# A7_FUNCTION3_-.net
KiCad netlist of a schematic drawn in Altium Designer
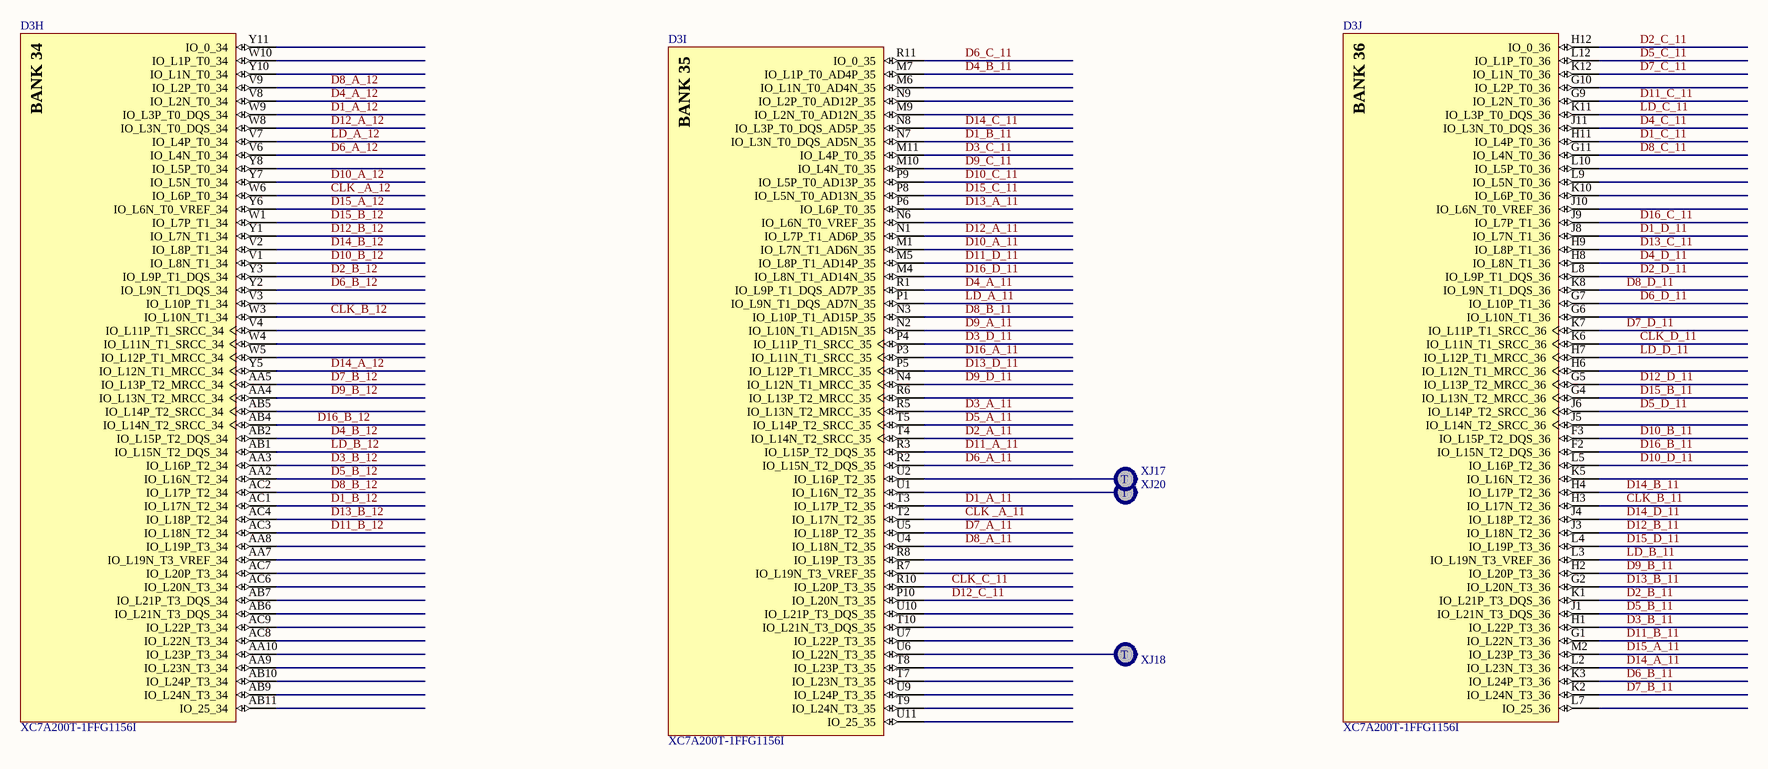
[diagram p0: A7_FUNCTION3 - Ⅱ.SchDoc]

(export (version "E")
  (design (tool "Eeschema 10.0.6"))
  (components
    (comp (ref "D3")
      (value "XC7A200T-1FFG1156I")
      (footprint "FFG1156")
      (description "Artix-7 FPGA, 500 User I/Os, 16 GTP, 1156-Ball BGA, Speed Grade 1, Industrial Grade, Pb-Free")
      (fields (field (name "GENERIC PART NUMBER") "XC7A200T") (field (name "MANUFACTURER") "Xilinx"))
      (libsource (lib "Xilinx Artix-7") (part "XC7A200T-1FFG1156I"))
    )
    (comp (ref "XJ17")
      (value "TESTPOINT")
      (footprint "TEST-pin")
      (description "测试点")
      (libsource (lib "Database_Libs1") (part "TESTPOINT"))
    )
    (comp (ref "XJ18")
      (value "TESTPOINT")
      (footprint "TEST-pin")
      (description "测试点")
      (libsource (lib "Database_Libs1") (part "TESTPOINT"))
    )
    (comp (ref "XJ20")
      (value "TESTPOINT")
      (footprint "TEST-pin")
      (description "测试点")
      (libsource (lib "Database_Libs1") (part "TESTPOINT"))
    )
  )
  (nets
    (net (code "1") (name "/CLK _A_11") (class "Default")
      (node (ref "D3") (pin "T2") (pinfunction "IO_L17N_T2_35_T2") (pintype "bidirectional"))
    )
    (net (code "2") (name "/CLK _A_12") (class "Default")
      (node (ref "D3") (pin "W6") (pinfunction "IO_L6P_T0_34_W6") (pintype "bidirectional"))
    )
    (net (code "3") (name "/CLK_B_11") (class "Default")
      (node (ref "D3") (pin "H3") (pinfunction "IO_L17N_T2_36_H3") (pintype "bidirectional"))
    )
    (net (code "4") (name "/CLK_B_12") (class "Default")
      (node (ref "D3") (pin "W3") (pinfunction "IO_L10N_T1_34_W3") (pintype "bidirectional"))
    )
    (net (code "5") (name "/CLK_C_11") (class "Default")
      (node (ref "D3") (pin "R10") (pinfunction "IO_L20P_T3_35_R10") (pintype "bidirectional"))
    )
    (net (code "6") (name "/CLK_D_11") (class "Default")
      (node (ref "D3") (pin "K6") (pinfunction "IO_L11N_T1_SRCC_36_K6") (pintype "bidirectional"))
    )
    (net (code "7") (name "/D1_A_11") (class "Default")
      (node (ref "D3") (pin "T3") (pinfunction "IO_L17P_T2_35_T3") (pintype "bidirectional"))
    )
    (net (code "8") (name "/D1_A_12") (class "Default")
      (node (ref "D3") (pin "W9") (pinfunction "IO_L3P_T0_DQS_34_W9") (pintype "bidirectional"))
    )
    (net (code "9") (name "/D1_B_11") (class "Default")
      (node (ref "D3") (pin "N7") (pinfunction "IO_L3N_T0_DQS_AD5N_35_N7") (pintype "bidirectional"))
    )
    (net (code "10") (name "/D1_B_12") (class "Default")
      (node (ref "D3") (pin "AC1") (pinfunction "IO_L17N_T2_34_AC1") (pintype "bidirectional"))
    )
    (net (code "11") (name "/D1_C_11") (class "Default")
      (node (ref "D3") (pin "H11") (pinfunction "IO_L4P_T0_36_H11") (pintype "bidirectional"))
    )
    (net (code "12") (name "/D1_D_11") (class "Default")
      (node (ref "D3") (pin "J8") (pinfunction "IO_L7N_T1_36_J8") (pintype "bidirectional"))
    )
    (net (code "13") (name "/D2_A_11") (class "Default")
      (node (ref "D3") (pin "T4") (pinfunction "IO_L14N_T2_SRCC_35_T4") (pintype "bidirectional"))
    )
    (net (code "14") (name "/D2_B_11") (class "Default")
      (node (ref "D3") (pin "K1") (pinfunction "IO_L21P_T3_DQS_36_K1") (pintype "bidirectional"))
    )
    (net (code "15") (name "/D2_B_12") (class "Default")
      (node (ref "D3") (pin "Y3") (pinfunction "IO_L9P_T1_DQS_34_Y3") (pintype "bidirectional"))
    )
    (net (code "16") (name "/D2_C_11") (class "Default")
      (node (ref "D3") (pin "H12") (pinfunction "IO_0_36_H12") (pintype "bidirectional"))
    )
    (net (code "17") (name "/D2_D_11") (class "Default")
      (node (ref "D3") (pin "L8") (pinfunction "IO_L9P_T1_DQS_36_L8") (pintype "bidirectional"))
    )
    (net (code "18") (name "/D3_A_11") (class "Default")
      (node (ref "D3") (pin "R5") (pinfunction "IO_L13N_T2_MRCC_35_R5") (pintype "bidirectional"))
    )
    (net (code "19") (name "/D3_B_11") (class "Default")
      (node (ref "D3") (pin "H1") (pinfunction "IO_L22P_T3_36_H1") (pintype "bidirectional"))
    )
    (net (code "20") (name "/D3_B_12") (class "Default")
      (node (ref "D3") (pin "AA3") (pinfunction "IO_L16P_T2_34_AA3") (pintype "bidirectional"))
    )
    (net (code "21") (name "/D3_C_11") (class "Default")
      (node (ref "D3") (pin "M11") (pinfunction "IO_L4P_T0_35_M11") (pintype "bidirectional"))
    )
    (net (code "22") (name "/D3_D_11") (class "Default")
      (node (ref "D3") (pin "P4") (pinfunction "IO_L11P_T1_SRCC_35_P4") (pintype "bidirectional"))
    )
    (net (code "23") (name "/D4_A_11") (class "Default")
      (node (ref "D3") (pin "R1") (pinfunction "IO_L9P_T1_DQS_AD7P_35_R1") (pintype "bidirectional"))
    )
    (net (code "24") (name "/D4_A_12") (class "Default")
      (node (ref "D3") (pin "V8") (pinfunction "IO_L2N_T0_34_V8") (pintype "bidirectional"))
    )
    (net (code "25") (name "/D4_B_11") (class "Default")
      (node (ref "D3") (pin "M7") (pinfunction "IO_L1P_T0_AD4P_35_M7") (pintype "bidirectional"))
    )
    (net (code "26") (name "/D4_B_12") (class "Default")
      (node (ref "D3") (pin "AB2") (pinfunction "IO_L15P_T2_DQS_34_AB2") (pintype "bidirectional"))
    )
    (net (code "27") (name "/D4_C_11") (class "Default")
      (node (ref "D3") (pin "J11") (pinfunction "IO_L3N_T0_DQS_36_J11") (pintype "bidirectional"))
    )
    (net (code "28") (name "/D4_D_11") (class "Default")
      (node (ref "D3") (pin "H8") (pinfunction "IO_L8N_T1_36_H8") (pintype "bidirectional"))
    )
    (net (code "29") (name "/D5_A_11") (class "Default")
      (node (ref "D3") (pin "T5") (pinfunction "IO_L14P_T2_SRCC_35_T5") (pintype "bidirectional"))
    )
    (net (code "30") (name "/D5_B_11") (class "Default")
      (node (ref "D3") (pin "J1") (pinfunction "IO_L21N_T3_DQS_36_J1") (pintype "bidirectional"))
    )
    (net (code "31") (name "/D5_B_12") (class "Default")
      (node (ref "D3") (pin "AA2") (pinfunction "IO_L16N_T2_34_AA2") (pintype "bidirectional"))
    )
    (net (code "32") (name "/D5_C_11") (class "Default")
      (node (ref "D3") (pin "L12") (pinfunction "IO_L1P_T0_36_L12") (pintype "bidirectional"))
    )
    (net (code "33") (name "/D5_D_11") (class "Default")
      (node (ref "D3") (pin "J6") (pinfunction "IO_L14P_T2_SRCC_36_J6") (pintype "bidirectional"))
    )
    (net (code "34") (name "/D6_A_11") (class "Default")
      (node (ref "D3") (pin "R2") (pinfunction "IO_L15N_T2_DQS_35_R2") (pintype "bidirectional"))
    )
    (net (code "35") (name "/D6_A_12") (class "Default")
      (node (ref "D3") (pin "V6") (pinfunction "IO_L4N_T0_34_V6") (pintype "bidirectional"))
    )
    (net (code "36") (name "/D6_B_11") (class "Default")
      (node (ref "D3") (pin "K3") (pinfunction "IO_L24P_T3_36_K3") (pintype "bidirectional"))
    )
    (net (code "37") (name "/D6_B_12") (class "Default")
      (node (ref "D3") (pin "Y2") (pinfunction "IO_L9N_T1_DQS_34_Y2") (pintype "bidirectional"))
    )
    (net (code "38") (name "/D6_C_11") (class "Default")
      (node (ref "D3") (pin "R11") (pinfunction "IO_0_35_R11") (pintype "bidirectional"))
    )
    (net (code "39") (name "/D6_D_11") (class "Default")
      (node (ref "D3") (pin "G7") (pinfunction "IO_L10P_T1_36_G7") (pintype "bidirectional"))
    )
    (net (code "40") (name "/D7_A_11") (class "Default")
      (node (ref "D3") (pin "U5") (pinfunction "IO_L18P_T2_35_U5") (pintype "bidirectional"))
    )
    (net (code "41") (name "/D7_B_11") (class "Default")
      (node (ref "D3") (pin "K2") (pinfunction "IO_L24N_T3_36_K2") (pintype "bidirectional"))
    )
    (net (code "42") (name "/D7_B_12") (class "Default")
      (node (ref "D3") (pin "AA5") (pinfunction "IO_L13P_T2_MRCC_34_AA5") (pintype "bidirectional"))
    )
    (net (code "43") (name "/D7_C_11") (class "Default")
      (node (ref "D3") (pin "K12") (pinfunction "IO_L1N_T0_36_K12") (pintype "bidirectional"))
    )
    (net (code "44") (name "/D7_D_11") (class "Default")
      (node (ref "D3") (pin "K7") (pinfunction "IO_L11P_T1_SRCC_36_K7") (pintype "bidirectional"))
    )
    (net (code "45") (name "/D8_A_11") (class "Default")
      (node (ref "D3") (pin "U4") (pinfunction "IO_L18N_T2_35_U4") (pintype "bidirectional"))
    )
    (net (code "46") (name "/D8_A_12") (class "Default")
      (node (ref "D3") (pin "V9") (pinfunction "IO_L2P_T0_34_V9") (pintype "bidirectional"))
    )
    (net (code "47") (name "/D8_B_11") (class "Default")
      (node (ref "D3") (pin "N3") (pinfunction "IO_L10P_T1_AD15P_35_N3") (pintype "bidirectional"))
    )
    (net (code "48") (name "/D8_B_12") (class "Default")
      (node (ref "D3") (pin "AC2") (pinfunction "IO_L17P_T2_34_AC2") (pintype "bidirectional"))
    )
    (net (code "49") (name "/D8_C_11") (class "Default")
      (node (ref "D3") (pin "G11") (pinfunction "IO_L4N_T0_36_G11") (pintype "bidirectional"))
    )
    (net (code "50") (name "/D8_D_11") (class "Default")
      (node (ref "D3") (pin "K8") (pinfunction "IO_L9N_T1_DQS_36_K8") (pintype "bidirectional"))
    )
    (net (code "51") (name "/D9_A_11") (class "Default")
      (node (ref "D3") (pin "N2") (pinfunction "IO_L10N_T1_AD15N_35_N2") (pintype "bidirectional"))
    )
    (net (code "52") (name "/D9_B_11") (class "Default")
      (node (ref "D3") (pin "H2") (pinfunction "IO_L20P_T3_36_H2") (pintype "bidirectional"))
    )
    (net (code "53") (name "/D9_B_12") (class "Default")
      (node (ref "D3") (pin "AA4") (pinfunction "IO_L13N_T2_MRCC_34_AA4") (pintype "bidirectional"))
    )
    (net (code "54") (name "/D9_C_11") (class "Default")
      (node (ref "D3") (pin "M10") (pinfunction "IO_L4N_T0_35_M10") (pintype "bidirectional"))
    )
    (net (code "55") (name "/D9_D_11") (class "Default")
      (node (ref "D3") (pin "N4") (pinfunction "IO_L12N_T1_MRCC_35_N4") (pintype "bidirectional"))
    )
    (net (code "56") (name "/D10_A_11") (class "Default")
      (node (ref "D3") (pin "M1") (pinfunction "IO_L7N_T1_AD6N_35_M1") (pintype "bidirectional"))
    )
    (net (code "57") (name "/D10_A_12") (class "Default")
      (node (ref "D3") (pin "Y7") (pinfunction "IO_L5N_T0_34_Y7") (pintype "bidirectional"))
    )
    (net (code "58") (name "/D10_B_11") (class "Default")
      (node (ref "D3") (pin "F3") (pinfunction "IO_L15P_T2_DQS_36_F3") (pintype "bidirectional"))
    )
    (net (code "59") (name "/D10_B_12") (class "Default")
      (node (ref "D3") (pin "V1") (pinfunction "IO_L8N_T1_34_V1") (pintype "bidirectional"))
    )
    (net (code "60") (name "/D10_C_11") (class "Default")
      (node (ref "D3") (pin "P9") (pinfunction "IO_L5P_T0_AD13P_35_P9") (pintype "bidirectional"))
    )
    (net (code "61") (name "/D10_D_11") (class "Default")
      (node (ref "D3") (pin "L5") (pinfunction "IO_L16P_T2_36_L5") (pintype "bidirectional"))
    )
    (net (code "62") (name "/D11_A_11") (class "Default")
      (node (ref "D3") (pin "R3") (pinfunction "IO_L15P_T2_DQS_35_R3") (pintype "bidirectional"))
    )
    (net (code "63") (name "/D11_B_11") (class "Default")
      (node (ref "D3") (pin "G1") (pinfunction "IO_L22N_T3_36_G1") (pintype "bidirectional"))
    )
    (net (code "64") (name "/D11_B_12") (class "Default")
      (node (ref "D3") (pin "AC3") (pinfunction "IO_L18N_T2_34_AC3") (pintype "bidirectional"))
    )
    (net (code "65") (name "/D11_C_11") (class "Default")
      (node (ref "D3") (pin "G9") (pinfunction "IO_L2N_T0_36_G9") (pintype "bidirectional"))
    )
    (net (code "66") (name "/D11_D_11") (class "Default")
      (node (ref "D3") (pin "M5") (pinfunction "IO_L8P_T1_AD14P_35_M5") (pintype "bidirectional"))
    )
    (net (code "67") (name "/D12_A_11") (class "Default")
      (node (ref "D3") (pin "N1") (pinfunction "IO_L7P_T1_AD6P_35_N1") (pintype "bidirectional"))
    )
    (net (code "68") (name "/D12_A_12") (class "Default")
      (node (ref "D3") (pin "W8") (pinfunction "IO_L3N_T0_DQS_34_W8") (pintype "bidirectional"))
    )
    (net (code "69") (name "/D12_B_11") (class "Default")
      (node (ref "D3") (pin "J3") (pinfunction "IO_L18N_T2_36_J3") (pintype "bidirectional"))
    )
    (net (code "70") (name "/D12_B_12") (class "Default")
      (node (ref "D3") (pin "Y1") (pinfunction "IO_L7N_T1_34_Y1") (pintype "bidirectional"))
    )
    (net (code "71") (name "/D12_C_11") (class "Default")
      (node (ref "D3") (pin "P10") (pinfunction "IO_L20N_T3_35_P10") (pintype "bidirectional"))
    )
    (net (code "72") (name "/D12_D_11") (class "Default")
      (node (ref "D3") (pin "G5") (pinfunction "IO_L13P_T2_MRCC_36_G5") (pintype "bidirectional"))
    )
    (net (code "73") (name "/D13_A_11") (class "Default")
      (node (ref "D3") (pin "P6") (pinfunction "IO_L6P_T0_35_P6") (pintype "bidirectional"))
    )
    (net (code "74") (name "/D13_B_11") (class "Default")
      (node (ref "D3") (pin "G2") (pinfunction "IO_L20N_T3_36_G2") (pintype "bidirectional"))
    )
    (net (code "75") (name "/D13_B_12") (class "Default")
      (node (ref "D3") (pin "AC4") (pinfunction "IO_L18P_T2_34_AC4") (pintype "bidirectional"))
    )
    (net (code "76") (name "/D13_C_11") (class "Default")
      (node (ref "D3") (pin "H9") (pinfunction "IO_L8P_T1_36_H9") (pintype "bidirectional"))
    )
    (net (code "77") (name "/D13_D_11") (class "Default")
      (node (ref "D3") (pin "P5") (pinfunction "IO_L12P_T1_MRCC_35_P5") (pintype "bidirectional"))
    )
    (net (code "78") (name "/D14_A_11") (class "Default")
      (node (ref "D3") (pin "L2") (pinfunction "IO_L23N_T3_36_L2") (pintype "bidirectional"))
    )
    (net (code "79") (name "/D14_A_12") (class "Default")
      (node (ref "D3") (pin "Y5") (pinfunction "IO_L12N_T1_MRCC_34_Y5") (pintype "bidirectional"))
    )
    (net (code "80") (name "/D14_B_11") (class "Default")
      (node (ref "D3") (pin "H4") (pinfunction "IO_L17P_T2_36_H4") (pintype "bidirectional"))
    )
    (net (code "81") (name "/D14_B_12") (class "Default")
      (node (ref "D3") (pin "V2") (pinfunction "IO_L8P_T1_34_V2") (pintype "bidirectional"))
    )
    (net (code "82") (name "/D14_C_11") (class "Default")
      (node (ref "D3") (pin "N8") (pinfunction "IO_L3P_T0_DQS_AD5P_35_N8") (pintype "bidirectional"))
    )
    (net (code "83") (name "/D14_D_11") (class "Default")
      (node (ref "D3") (pin "J4") (pinfunction "IO_L18P_T2_36_J4") (pintype "bidirectional"))
    )
    (net (code "84") (name "/D15_A_11") (class "Default")
      (node (ref "D3") (pin "M2") (pinfunction "IO_L23P_T3_36_M2") (pintype "bidirectional"))
    )
    (net (code "85") (name "/D15_A_12") (class "Default")
      (node (ref "D3") (pin "Y6") (pinfunction "IO_L6N_T0_VREF_34_Y6") (pintype "bidirectional"))
    )
    (net (code "86") (name "/D15_B_11") (class "Default")
      (node (ref "D3") (pin "G4") (pinfunction "IO_L13N_T2_MRCC_36_G4") (pintype "bidirectional"))
    )
    (net (code "87") (name "/D15_B_12") (class "Default")
      (node (ref "D3") (pin "W1") (pinfunction "IO_L7P_T1_34_W1") (pintype "bidirectional"))
    )
    (net (code "88") (name "/D15_C_11") (class "Default")
      (node (ref "D3") (pin "P8") (pinfunction "IO_L5N_T0_AD13N_35_P8") (pintype "bidirectional"))
    )
    (net (code "89") (name "/D15_D_11") (class "Default")
      (node (ref "D3") (pin "L4") (pinfunction "IO_L19P_T3_36_L4") (pintype "bidirectional"))
    )
    (net (code "90") (name "/D16_A_11") (class "Default")
      (node (ref "D3") (pin "P3") (pinfunction "IO_L11N_T1_SRCC_35_P3") (pintype "bidirectional"))
    )
    (net (code "91") (name "/D16_B_11") (class "Default")
      (node (ref "D3") (pin "F2") (pinfunction "IO_L15N_T2_DQS_36_F2") (pintype "bidirectional"))
    )
    (net (code "92") (name "/D16_B_12") (class "Default")
      (node (ref "D3") (pin "AB4") (pinfunction "IO_L14N_T2_SRCC_34_AB4") (pintype "bidirectional"))
    )
    (net (code "93") (name "/D16_C_11") (class "Default")
      (node (ref "D3") (pin "J9") (pinfunction "IO_L7P_T1_36_J9") (pintype "bidirectional"))
    )
    (net (code "94") (name "/D16_D_11") (class "Default")
      (node (ref "D3") (pin "M4") (pinfunction "IO_L8N_T1_AD14N_35_M4") (pintype "bidirectional"))
    )
    (net (code "95") (name "/LD_A_11") (class "Default")
      (node (ref "D3") (pin "P1") (pinfunction "IO_L9N_T1_DQS_AD7N_35_P1") (pintype "bidirectional"))
    )
    (net (code "96") (name "/LD_A_12") (class "Default")
      (node (ref "D3") (pin "V7") (pinfunction "IO_L4P_T0_34_V7") (pintype "bidirectional"))
    )
    (net (code "97") (name "/LD_B_11") (class "Default")
      (node (ref "D3") (pin "L3") (pinfunction "IO_L19N_T3_VREF_36_L3") (pintype "bidirectional"))
    )
    (net (code "98") (name "/LD_B_12") (class "Default")
      (node (ref "D3") (pin "AB1") (pinfunction "IO_L15N_T2_DQS_34_AB1") (pintype "bidirectional"))
    )
    (net (code "99") (name "/LD_C_11") (class "Default")
      (node (ref "D3") (pin "K11") (pinfunction "IO_L3P_T0_DQS_36_K11") (pintype "bidirectional"))
    )
    (net (code "100") (name "/LD_D_11") (class "Default")
      (node (ref "D3") (pin "H7") (pinfunction "IO_L12P_T1_MRCC_36_H7") (pintype "bidirectional"))
    )
    (net (code "101") (name "Net-(D3I-IO_L16N_T2_35)") (class "Default")
      (node (ref "D3") (pin "U1") (pinfunction "IO_L16N_T2_35_U1") (pintype "bidirectional"))
      (node (ref "XJ20") (pin "1") (pinfunction "T_1") (pintype "passive"))
    )
    (net (code "102") (name "Net-(D3I-IO_L16P_T2_35)") (class "Default")
      (node (ref "D3") (pin "U2") (pinfunction "IO_L16P_T2_35_U2") (pintype "bidirectional"))
      (node (ref "XJ17") (pin "1") (pinfunction "T_1") (pintype "passive"))
    )
    (net (code "103") (name "Net-(D3I-IO_L22N_T3_35)") (class "Default")
      (node (ref "D3") (pin "U6") (pinfunction "IO_L22N_T3_35_U6") (pintype "bidirectional"))
      (node (ref "XJ18") (pin "1") (pinfunction "T_1") (pintype "passive"))
    )
    (net (code "104") (name "unconnected-(D3H-IO_0_34-PadY11)") (class "Default")
      (node (ref "D3") (pin "Y11") (pinfunction "IO_0_34_Y11") (pintype "bidirectional"))
    )
    (net (code "105") (name "unconnected-(D3H-IO_25_34-PadAB11)") (class "Default")
      (node (ref "D3") (pin "AB11") (pinfunction "IO_25_34_AB11") (pintype "bidirectional"))
    )
    (net (code "106") (name "unconnected-(D3H-IO_L1N_T0_34-PadY10)") (class "Default")
      (node (ref "D3") (pin "Y10") (pinfunction "IO_L1N_T0_34_Y10") (pintype "bidirectional"))
    )
    (net (code "107") (name "unconnected-(D3H-IO_L1P_T0_34-PadW10)") (class "Default")
      (node (ref "D3") (pin "W10") (pinfunction "IO_L1P_T0_34_W10") (pintype "bidirectional"))
    )
    (net (code "108") (name "unconnected-(D3H-IO_L5P_T0_34-PadY8)") (class "Default")
      (node (ref "D3") (pin "Y8") (pinfunction "IO_L5P_T0_34_Y8") (pintype "bidirectional"))
    )
    (net (code "109") (name "unconnected-(D3H-IO_L10P_T1_34-PadV3)") (class "Default")
      (node (ref "D3") (pin "V3") (pinfunction "IO_L10P_T1_34_V3") (pintype "bidirectional"))
    )
    (net (code "110") (name "unconnected-(D3H-IO_L11N_T1_SRCC_34-PadW4)") (class "Default")
      (node (ref "D3") (pin "W4") (pinfunction "IO_L11N_T1_SRCC_34_W4") (pintype "bidirectional"))
    )
    (net (code "111") (name "unconnected-(D3H-IO_L11P_T1_SRCC_34-PadV4)") (class "Default")
      (node (ref "D3") (pin "V4") (pinfunction "IO_L11P_T1_SRCC_34_V4") (pintype "bidirectional"))
    )
    (net (code "112") (name "unconnected-(D3H-IO_L12P_T1_MRCC_34-PadW5)") (class "Default")
      (node (ref "D3") (pin "W5") (pinfunction "IO_L12P_T1_MRCC_34_W5") (pintype "bidirectional"))
    )
    (net (code "113") (name "unconnected-(D3H-IO_L14P_T2_SRCC_34-PadAB5)") (class "Default")
      (node (ref "D3") (pin "AB5") (pinfunction "IO_L14P_T2_SRCC_34_AB5") (pintype "bidirectional"))
    )
    (net (code "114") (name "unconnected-(D3H-IO_L19N_T3_VREF_34-PadAA7)") (class "Default")
      (node (ref "D3") (pin "AA7") (pinfunction "IO_L19N_T3_VREF_34_AA7") (pintype "bidirectional"))
    )
    (net (code "115") (name "unconnected-(D3H-IO_L19P_T3_34-PadAA8)") (class "Default")
      (node (ref "D3") (pin "AA8") (pinfunction "IO_L19P_T3_34_AA8") (pintype "bidirectional"))
    )
    (net (code "116") (name "unconnected-(D3H-IO_L20N_T3_34-PadAC6)") (class "Default")
      (node (ref "D3") (pin "AC6") (pinfunction "IO_L20N_T3_34_AC6") (pintype "bidirectional"))
    )
    (net (code "117") (name "unconnected-(D3H-IO_L20P_T3_34-PadAC7)") (class "Default")
      (node (ref "D3") (pin "AC7") (pinfunction "IO_L20P_T3_34_AC7") (pintype "bidirectional"))
    )
    (net (code "118") (name "unconnected-(D3H-IO_L21N_T3_DQS_34-PadAB6)") (class "Default")
      (node (ref "D3") (pin "AB6") (pinfunction "IO_L21N_T3_DQS_34_AB6") (pintype "bidirectional"))
    )
    (net (code "119") (name "unconnected-(D3H-IO_L21P_T3_DQS_34-PadAB7)") (class "Default")
      (node (ref "D3") (pin "AB7") (pinfunction "IO_L21P_T3_DQS_34_AB7") (pintype "bidirectional"))
    )
    (net (code "120") (name "unconnected-(D3H-IO_L22N_T3_34-PadAC8)") (class "Default")
      (node (ref "D3") (pin "AC8") (pinfunction "IO_L22N_T3_34_AC8") (pintype "bidirectional"))
    )
    (net (code "121") (name "unconnected-(D3H-IO_L22P_T3_34-PadAC9)") (class "Default")
      (node (ref "D3") (pin "AC9") (pinfunction "IO_L22P_T3_34_AC9") (pintype "bidirectional"))
    )
    (net (code "122") (name "unconnected-(D3H-IO_L23N_T3_34-PadAA9)") (class "Default")
      (node (ref "D3") (pin "AA9") (pinfunction "IO_L23N_T3_34_AA9") (pintype "bidirectional"))
    )
    (net (code "123") (name "unconnected-(D3H-IO_L23P_T3_34-PadAA10)") (class "Default")
      (node (ref "D3") (pin "AA10") (pinfunction "IO_L23P_T3_34_AA10") (pintype "bidirectional"))
    )
    (net (code "124") (name "unconnected-(D3H-IO_L24N_T3_34-PadAB9)") (class "Default")
      (node (ref "D3") (pin "AB9") (pinfunction "IO_L24N_T3_34_AB9") (pintype "bidirectional"))
    )
    (net (code "125") (name "unconnected-(D3H-IO_L24P_T3_34-PadAB10)") (class "Default")
      (node (ref "D3") (pin "AB10") (pinfunction "IO_L24P_T3_34_AB10") (pintype "bidirectional"))
    )
    (net (code "126") (name "unconnected-(D3I-IO_25_35-PadU11)") (class "Default")
      (node (ref "D3") (pin "U11") (pinfunction "IO_25_35_U11") (pintype "bidirectional"))
    )
    (net (code "127") (name "unconnected-(D3I-IO_L1N_T0_AD4N_35-PadM6)") (class "Default")
      (node (ref "D3") (pin "M6") (pinfunction "IO_L1N_T0_AD4N_35_M6") (pintype "bidirectional"))
    )
    (net (code "128") (name "unconnected-(D3I-IO_L2N_T0_AD12N_35-PadM9)") (class "Default")
      (node (ref "D3") (pin "M9") (pinfunction "IO_L2N_T0_AD12N_35_M9") (pintype "bidirectional"))
    )
    (net (code "129") (name "unconnected-(D3I-IO_L2P_T0_AD12P_35-PadN9)") (class "Default")
      (node (ref "D3") (pin "N9") (pinfunction "IO_L2P_T0_AD12P_35_N9") (pintype "bidirectional"))
    )
    (net (code "130") (name "unconnected-(D3I-IO_L6N_T0_VREF_35-PadN6)") (class "Default")
      (node (ref "D3") (pin "N6") (pinfunction "IO_L6N_T0_VREF_35_N6") (pintype "bidirectional"))
    )
    (net (code "131") (name "unconnected-(D3I-IO_L13P_T2_MRCC_35-PadR6)") (class "Default")
      (node (ref "D3") (pin "R6") (pinfunction "IO_L13P_T2_MRCC_35_R6") (pintype "bidirectional"))
    )
    (net (code "132") (name "unconnected-(D3I-IO_L19N_T3_VREF_35-PadR7)") (class "Default")
      (node (ref "D3") (pin "R7") (pinfunction "IO_L19N_T3_VREF_35_R7") (pintype "bidirectional"))
    )
    (net (code "133") (name "unconnected-(D3I-IO_L19P_T3_35-PadR8)") (class "Default")
      (node (ref "D3") (pin "R8") (pinfunction "IO_L19P_T3_35_R8") (pintype "bidirectional"))
    )
    (net (code "134") (name "unconnected-(D3I-IO_L21N_T3_DQS_35-PadT10)") (class "Default")
      (node (ref "D3") (pin "T10") (pinfunction "IO_L21N_T3_DQS_35_T10") (pintype "bidirectional"))
    )
    (net (code "135") (name "unconnected-(D3I-IO_L21P_T3_DQS_35-PadU10)") (class "Default")
      (node (ref "D3") (pin "U10") (pinfunction "IO_L21P_T3_DQS_35_U10") (pintype "bidirectional"))
    )
    (net (code "136") (name "unconnected-(D3I-IO_L22P_T3_35-PadU7)") (class "Default")
      (node (ref "D3") (pin "U7") (pinfunction "IO_L22P_T3_35_U7") (pintype "bidirectional"))
    )
    (net (code "137") (name "unconnected-(D3I-IO_L23N_T3_35-PadT7)") (class "Default")
      (node (ref "D3") (pin "T7") (pinfunction "IO_L23N_T3_35_T7") (pintype "bidirectional"))
    )
    (net (code "138") (name "unconnected-(D3I-IO_L23P_T3_35-PadT8)") (class "Default")
      (node (ref "D3") (pin "T8") (pinfunction "IO_L23P_T3_35_T8") (pintype "bidirectional"))
    )
    (net (code "139") (name "unconnected-(D3I-IO_L24N_T3_35-PadT9)") (class "Default")
      (node (ref "D3") (pin "T9") (pinfunction "IO_L24N_T3_35_T9") (pintype "bidirectional"))
    )
    (net (code "140") (name "unconnected-(D3I-IO_L24P_T3_35-PadU9)") (class "Default")
      (node (ref "D3") (pin "U9") (pinfunction "IO_L24P_T3_35_U9") (pintype "bidirectional"))
    )
    (net (code "141") (name "unconnected-(D3J-IO_25_36-PadL7)") (class "Default")
      (node (ref "D3") (pin "L7") (pinfunction "IO_25_36_L7") (pintype "bidirectional"))
    )
    (net (code "142") (name "unconnected-(D3J-IO_L2P_T0_36-PadG10)") (class "Default")
      (node (ref "D3") (pin "G10") (pinfunction "IO_L2P_T0_36_G10") (pintype "bidirectional"))
    )
    (net (code "143") (name "unconnected-(D3J-IO_L5N_T0_36-PadL9)") (class "Default")
      (node (ref "D3") (pin "L9") (pinfunction "IO_L5N_T0_36_L9") (pintype "bidirectional"))
    )
    (net (code "144") (name "unconnected-(D3J-IO_L5P_T0_36-PadL10)") (class "Default")
      (node (ref "D3") (pin "L10") (pinfunction "IO_L5P_T0_36_L10") (pintype "bidirectional"))
    )
    (net (code "145") (name "unconnected-(D3J-IO_L6N_T0_VREF_36-PadJ10)") (class "Default")
      (node (ref "D3") (pin "J10") (pinfunction "IO_L6N_T0_VREF_36_J10") (pintype "bidirectional"))
    )
    (net (code "146") (name "unconnected-(D3J-IO_L6P_T0_36-PadK10)") (class "Default")
      (node (ref "D3") (pin "K10") (pinfunction "IO_L6P_T0_36_K10") (pintype "bidirectional"))
    )
    (net (code "147") (name "unconnected-(D3J-IO_L10N_T1_36-PadG6)") (class "Default")
      (node (ref "D3") (pin "G6") (pinfunction "IO_L10N_T1_36_G6") (pintype "bidirectional"))
    )
    (net (code "148") (name "unconnected-(D3J-IO_L12N_T1_MRCC_36-PadH6)") (class "Default")
      (node (ref "D3") (pin "H6") (pinfunction "IO_L12N_T1_MRCC_36_H6") (pintype "bidirectional"))
    )
    (net (code "149") (name "unconnected-(D3J-IO_L14N_T2_SRCC_36-PadJ5)") (class "Default")
      (node (ref "D3") (pin "J5") (pinfunction "IO_L14N_T2_SRCC_36_J5") (pintype "bidirectional"))
    )
    (net (code "150") (name "unconnected-(D3J-IO_L16N_T2_36-PadK5)") (class "Default")
      (node (ref "D3") (pin "K5") (pinfunction "IO_L16N_T2_36_K5") (pintype "bidirectional"))
    )
  )
)
